# PMOD_JP_KB.net
KiCad netlist of a schematic drawn in EAGLE
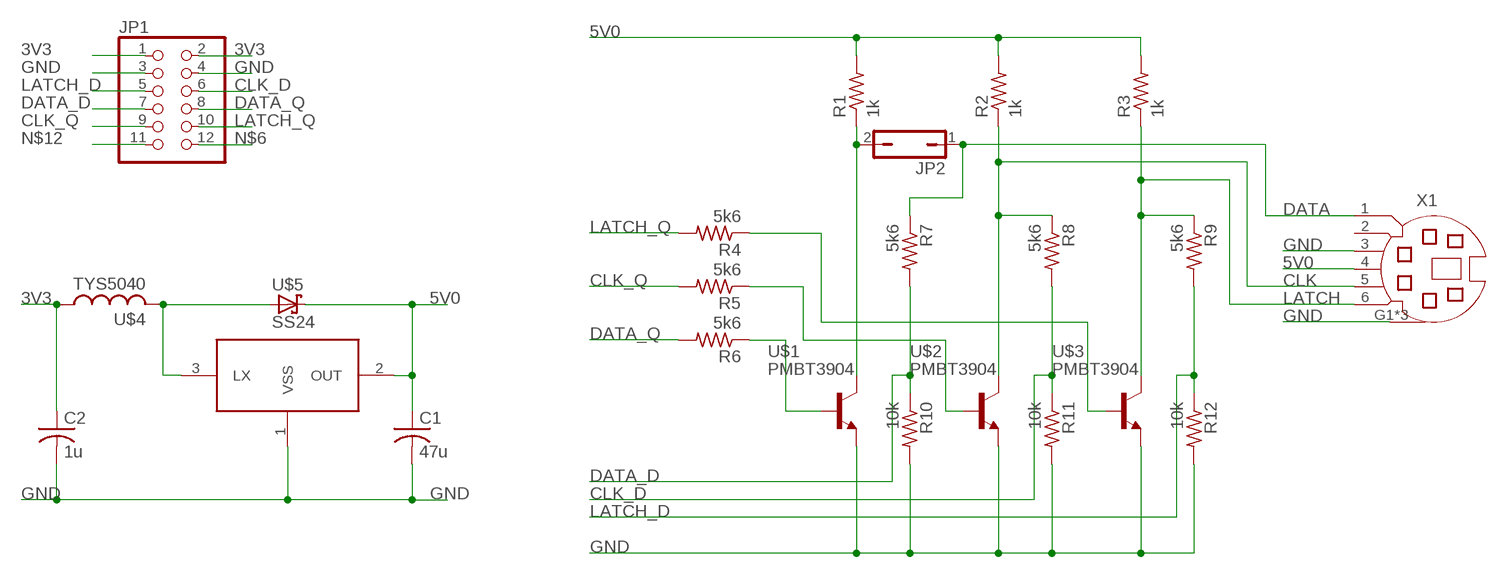
[diagram p0: schematic, sheet 1]

(export (version "E")
  (design (tool "Eeschema 10.0.6"))
  (components
    (comp (ref "C1")
      (value "47u")
      (footprint "eagle-import:C1206K")
      (libsource (lib "eagle-import") (part "C-USC1206K"))
    )
    (comp (ref "C2")
      (value "1u")
      (footprint "eagle-import:C0805K")
      (libsource (lib "eagle-import") (part "C-USC0805K"))
    )
    (comp (ref "JP1")
      (value "PINHD-2X6/90")
      (footprint "eagle-import:2X06_90")
      (libsource (lib "eagle-import") (part "PINHD-2X6/90"))
    )
    (comp (ref "JP2")
      (value "JP1Q")
      (footprint "eagle-import:JP1")
      (libsource (lib "eagle-import") (part "JP1Q"))
    )
    (comp (ref "R1")
      (value "1k")
      (footprint "eagle-import:R0805")
      (libsource (lib "eagle-import") (part "R-US_R0805"))
    )
    (comp (ref "R2")
      (value "1k")
      (footprint "eagle-import:R0805")
      (libsource (lib "eagle-import") (part "R-US_R0805"))
    )
    (comp (ref "R3")
      (value "1k")
      (footprint "eagle-import:R0805")
      (libsource (lib "eagle-import") (part "R-US_R0805"))
    )
    (comp (ref "R4")
      (value "5k6")
      (footprint "eagle-import:R0805")
      (libsource (lib "eagle-import") (part "R-US_R0805"))
    )
    (comp (ref "R5")
      (value "5k6")
      (footprint "eagle-import:R0805")
      (libsource (lib "eagle-import") (part "R-US_R0805"))
    )
    (comp (ref "R6")
      (value "5k6")
      (footprint "eagle-import:R0805")
      (libsource (lib "eagle-import") (part "R-US_R0805"))
    )
    (comp (ref "R7")
      (value "5k6")
      (footprint "eagle-import:R0805")
      (libsource (lib "eagle-import") (part "R-US_R0805"))
    )
    (comp (ref "R8")
      (value "5k6")
      (footprint "eagle-import:R0805")
      (libsource (lib "eagle-import") (part "R-US_R0805"))
    )
    (comp (ref "R9")
      (value "5k6")
      (footprint "eagle-import:R0805")
      (libsource (lib "eagle-import") (part "R-US_R0805"))
    )
    (comp (ref "R10")
      (value "10k")
      (footprint "eagle-import:R0805")
      (libsource (lib "eagle-import") (part "R-US_R0805"))
    )
    (comp (ref "R11")
      (value "10k")
      (footprint "eagle-import:R0805")
      (libsource (lib "eagle-import") (part "R-US_R0805"))
    )
    (comp (ref "R12")
      (value "10k")
      (footprint "eagle-import:R0805")
      (libsource (lib "eagle-import") (part "R-US_R0805"))
    )
    (comp (ref "U$1")
      (value "PMBT3904")
      (footprint "eagle-import:SOT23")
      (libsource (lib "eagle-import") (part "PMBT3904"))
    )
    (comp (ref "U$2")
      (value "PMBT3904")
      (footprint "eagle-import:SOT23")
      (libsource (lib "eagle-import") (part "PMBT3904"))
    )
    (comp (ref "U$3")
      (value "PMBT3904")
      (footprint "eagle-import:SOT23")
      (libsource (lib "eagle-import") (part "PMBT3904"))
    )
    (comp (ref "U$4")
      (value "TYS5040")
      (footprint "eagle-import:TYS5040")
      (libsource (lib "eagle-import") (part "TYS5040"))
    )
    (comp (ref "U$5")
      (value "SS24")
      (footprint "eagle-import:SMA-DO214AC")
      (libsource (lib "eagle-import") (part "SS24"))
    )
    (comp (ref "U$6")
      (value "ME2108A")
      (footprint "eagle-import:SOT89")
      (libsource (lib "eagle-import") (part "ME2108A"))
    )
    (comp (ref "X1")
      (value "MD06SS")
      (footprint "eagle-import:MDIN06SS")
      (libsource (lib "eagle-import") (part "MD06SS"))
    )
  )
  (nets
    (net (code "1") (name "/3V3") (class "Default")
      (node (ref "C2") (pin "1") (pinfunction "1_1") (pintype "passive"))
      (node (ref "JP1") (pin "1") (pinfunction "1_1") (pintype "passive"))
      (node (ref "JP1") (pin "2") (pinfunction "2_2") (pintype "passive"))
      (node (ref "U$4") (pin "P$1") (pinfunction "1_P$1") (pintype "passive"))
    )
    (net (code "2") (name "/5V0") (class "Default")
      (node (ref "C1") (pin "1") (pinfunction "1_1") (pintype "passive"))
      (node (ref "R1") (pin "2") (pinfunction "2_2") (pintype "passive"))
      (node (ref "R2") (pin "2") (pinfunction "2_2") (pintype "passive"))
      (node (ref "R3") (pin "2") (pinfunction "2_2") (pintype "passive"))
      (node (ref "U$5") (pin "K") (pinfunction "C_K") (pintype "passive"))
      (node (ref "U$6") (pin "2") (pinfunction "OUT_2") (pintype "bidirectional"))
      (node (ref "X1") (pin "4") (pinfunction "4_4") (pintype "passive"))
    )
    (net (code "3") (name "/CLK") (class "Default")
      (node (ref "R2") (pin "1") (pinfunction "1_1") (pintype "passive"))
      (node (ref "R8") (pin "1") (pinfunction "1_1") (pintype "passive"))
      (node (ref "U$2") (pin "3") (pinfunction "C_3") (pintype "passive"))
      (node (ref "X1") (pin "5") (pinfunction "5_5") (pintype "passive"))
    )
    (net (code "4") (name "/CLK_D") (class "Default")
      (node (ref "JP1") (pin "6") (pinfunction "6_6") (pintype "passive"))
      (node (ref "R11") (pin "1") (pinfunction "1_1") (pintype "passive"))
      (node (ref "R8") (pin "2") (pinfunction "2_2") (pintype "passive"))
    )
    (net (code "5") (name "/CLK_Q") (class "Default")
      (node (ref "JP1") (pin "9") (pinfunction "9_9") (pintype "passive"))
      (node (ref "R5") (pin "2") (pinfunction "2_2") (pintype "passive"))
    )
    (net (code "6") (name "/DATA") (class "Default")
      (node (ref "JP2") (pin "1") (pinfunction "1_1") (pintype "passive"))
      (node (ref "R7") (pin "1") (pinfunction "1_1") (pintype "passive"))
      (node (ref "X1") (pin "1") (pinfunction "1_1") (pintype "passive"))
    )
    (net (code "7") (name "/DATA_D") (class "Default")
      (node (ref "JP1") (pin "7") (pinfunction "7_7") (pintype "passive"))
      (node (ref "R10") (pin "1") (pinfunction "1_1") (pintype "passive"))
      (node (ref "R7") (pin "2") (pinfunction "2_2") (pintype "passive"))
    )
    (net (code "8") (name "/DATA_Q") (class "Default")
      (node (ref "JP1") (pin "8") (pinfunction "8_8") (pintype "passive"))
      (node (ref "R6") (pin "2") (pinfunction "2_2") (pintype "passive"))
    )
    (net (code "9") (name "/GND") (class "Default")
      (node (ref "C1") (pin "2") (pinfunction "2_2") (pintype "passive"))
      (node (ref "C2") (pin "2") (pinfunction "2_2") (pintype "passive"))
      (node (ref "JP1") (pin "3") (pinfunction "3_3") (pintype "passive"))
      (node (ref "JP1") (pin "4") (pinfunction "4_4") (pintype "passive"))
      (node (ref "R10") (pin "2") (pinfunction "2_2") (pintype "passive"))
      (node (ref "R11") (pin "2") (pinfunction "2_2") (pintype "passive"))
      (node (ref "R12") (pin "2") (pinfunction "2_2") (pintype "passive"))
      (node (ref "U$1") (pin "2") (pinfunction "E_2") (pintype "passive"))
      (node (ref "U$2") (pin "2") (pinfunction "E_2") (pintype "passive"))
      (node (ref "U$3") (pin "2") (pinfunction "E_2") (pintype "passive"))
      (node (ref "U$6") (pin "1") (pinfunction "VSS_1") (pintype "bidirectional"))
      (node (ref "X1") (pin "3") (pinfunction "3_3") (pintype "passive"))
      (node (ref "X1") (pin "G1") (pinfunction "G_G1") (pintype "bidirectional"))
      (node (ref "X1") (pin "G2") (pinfunction "G_G2") (pintype "bidirectional"))
      (node (ref "X1") (pin "G3") (pinfunction "G_G3") (pintype "bidirectional"))
    )
    (net (code "10") (name "/LATCH") (class "Default")
      (node (ref "R3") (pin "1") (pinfunction "1_1") (pintype "passive"))
      (node (ref "R9") (pin "1") (pinfunction "1_1") (pintype "passive"))
      (node (ref "U$3") (pin "3") (pinfunction "C_3") (pintype "passive"))
      (node (ref "X1") (pin "6") (pinfunction "6_6") (pintype "passive"))
    )
    (net (code "11") (name "/LATCH_D") (class "Default")
      (node (ref "JP1") (pin "5") (pinfunction "5_5") (pintype "passive"))
      (node (ref "R12") (pin "1") (pinfunction "1_1") (pintype "passive"))
      (node (ref "R9") (pin "2") (pinfunction "2_2") (pintype "passive"))
    )
    (net (code "12") (name "/LATCH_Q") (class "Default")
      (node (ref "JP1") (pin "10") (pinfunction "10_10") (pintype "passive"))
      (node (ref "R4") (pin "2") (pinfunction "2_2") (pintype "passive"))
    )
    (net (code "13") (name "/N$6") (class "Default")
      (node (ref "JP1") (pin "12") (pinfunction "12_12") (pintype "passive"))
    )
    (net (code "14") (name "/N$12") (class "Default")
      (node (ref "JP1") (pin "11") (pinfunction "11_11") (pintype "passive"))
    )
    (net (code "15") (name "Net-(U$1-B)") (class "Default")
      (node (ref "R6") (pin "1") (pinfunction "1_1") (pintype "passive"))
      (node (ref "U$1") (pin "1") (pinfunction "B_1") (pintype "passive"))
    )
    (net (code "16") (name "Net-(U$1-C)") (class "Default")
      (node (ref "JP2") (pin "2") (pinfunction "2_2") (pintype "passive"))
      (node (ref "R1") (pin "1") (pinfunction "1_1") (pintype "passive"))
      (node (ref "U$1") (pin "3") (pinfunction "C_3") (pintype "passive"))
    )
    (net (code "17") (name "Net-(U$2-B)") (class "Default")
      (node (ref "R5") (pin "1") (pinfunction "1_1") (pintype "passive"))
      (node (ref "U$2") (pin "1") (pinfunction "B_1") (pintype "passive"))
    )
    (net (code "18") (name "Net-(U$3-B)") (class "Default")
      (node (ref "R4") (pin "1") (pinfunction "1_1") (pintype "passive"))
      (node (ref "U$3") (pin "1") (pinfunction "B_1") (pintype "passive"))
    )
    (net (code "19") (name "Net-(U$4-2)") (class "Default")
      (node (ref "U$4") (pin "P$2") (pinfunction "2_P$2") (pintype "passive"))
      (node (ref "U$5") (pin "A") (pinfunction "A_A") (pintype "passive"))
      (node (ref "U$6") (pin "3") (pinfunction "LX_3") (pintype "bidirectional"))
    )
    (net (code "20") (name "unconnected-(X1-Pad2)") (class "Default")
      (node (ref "X1") (pin "2") (pinfunction "2_2") (pintype "passive"))
    )
  )
)
